# SOURCE_POWER.net
KiCad netlist of a schematic drawn in Altium Designer
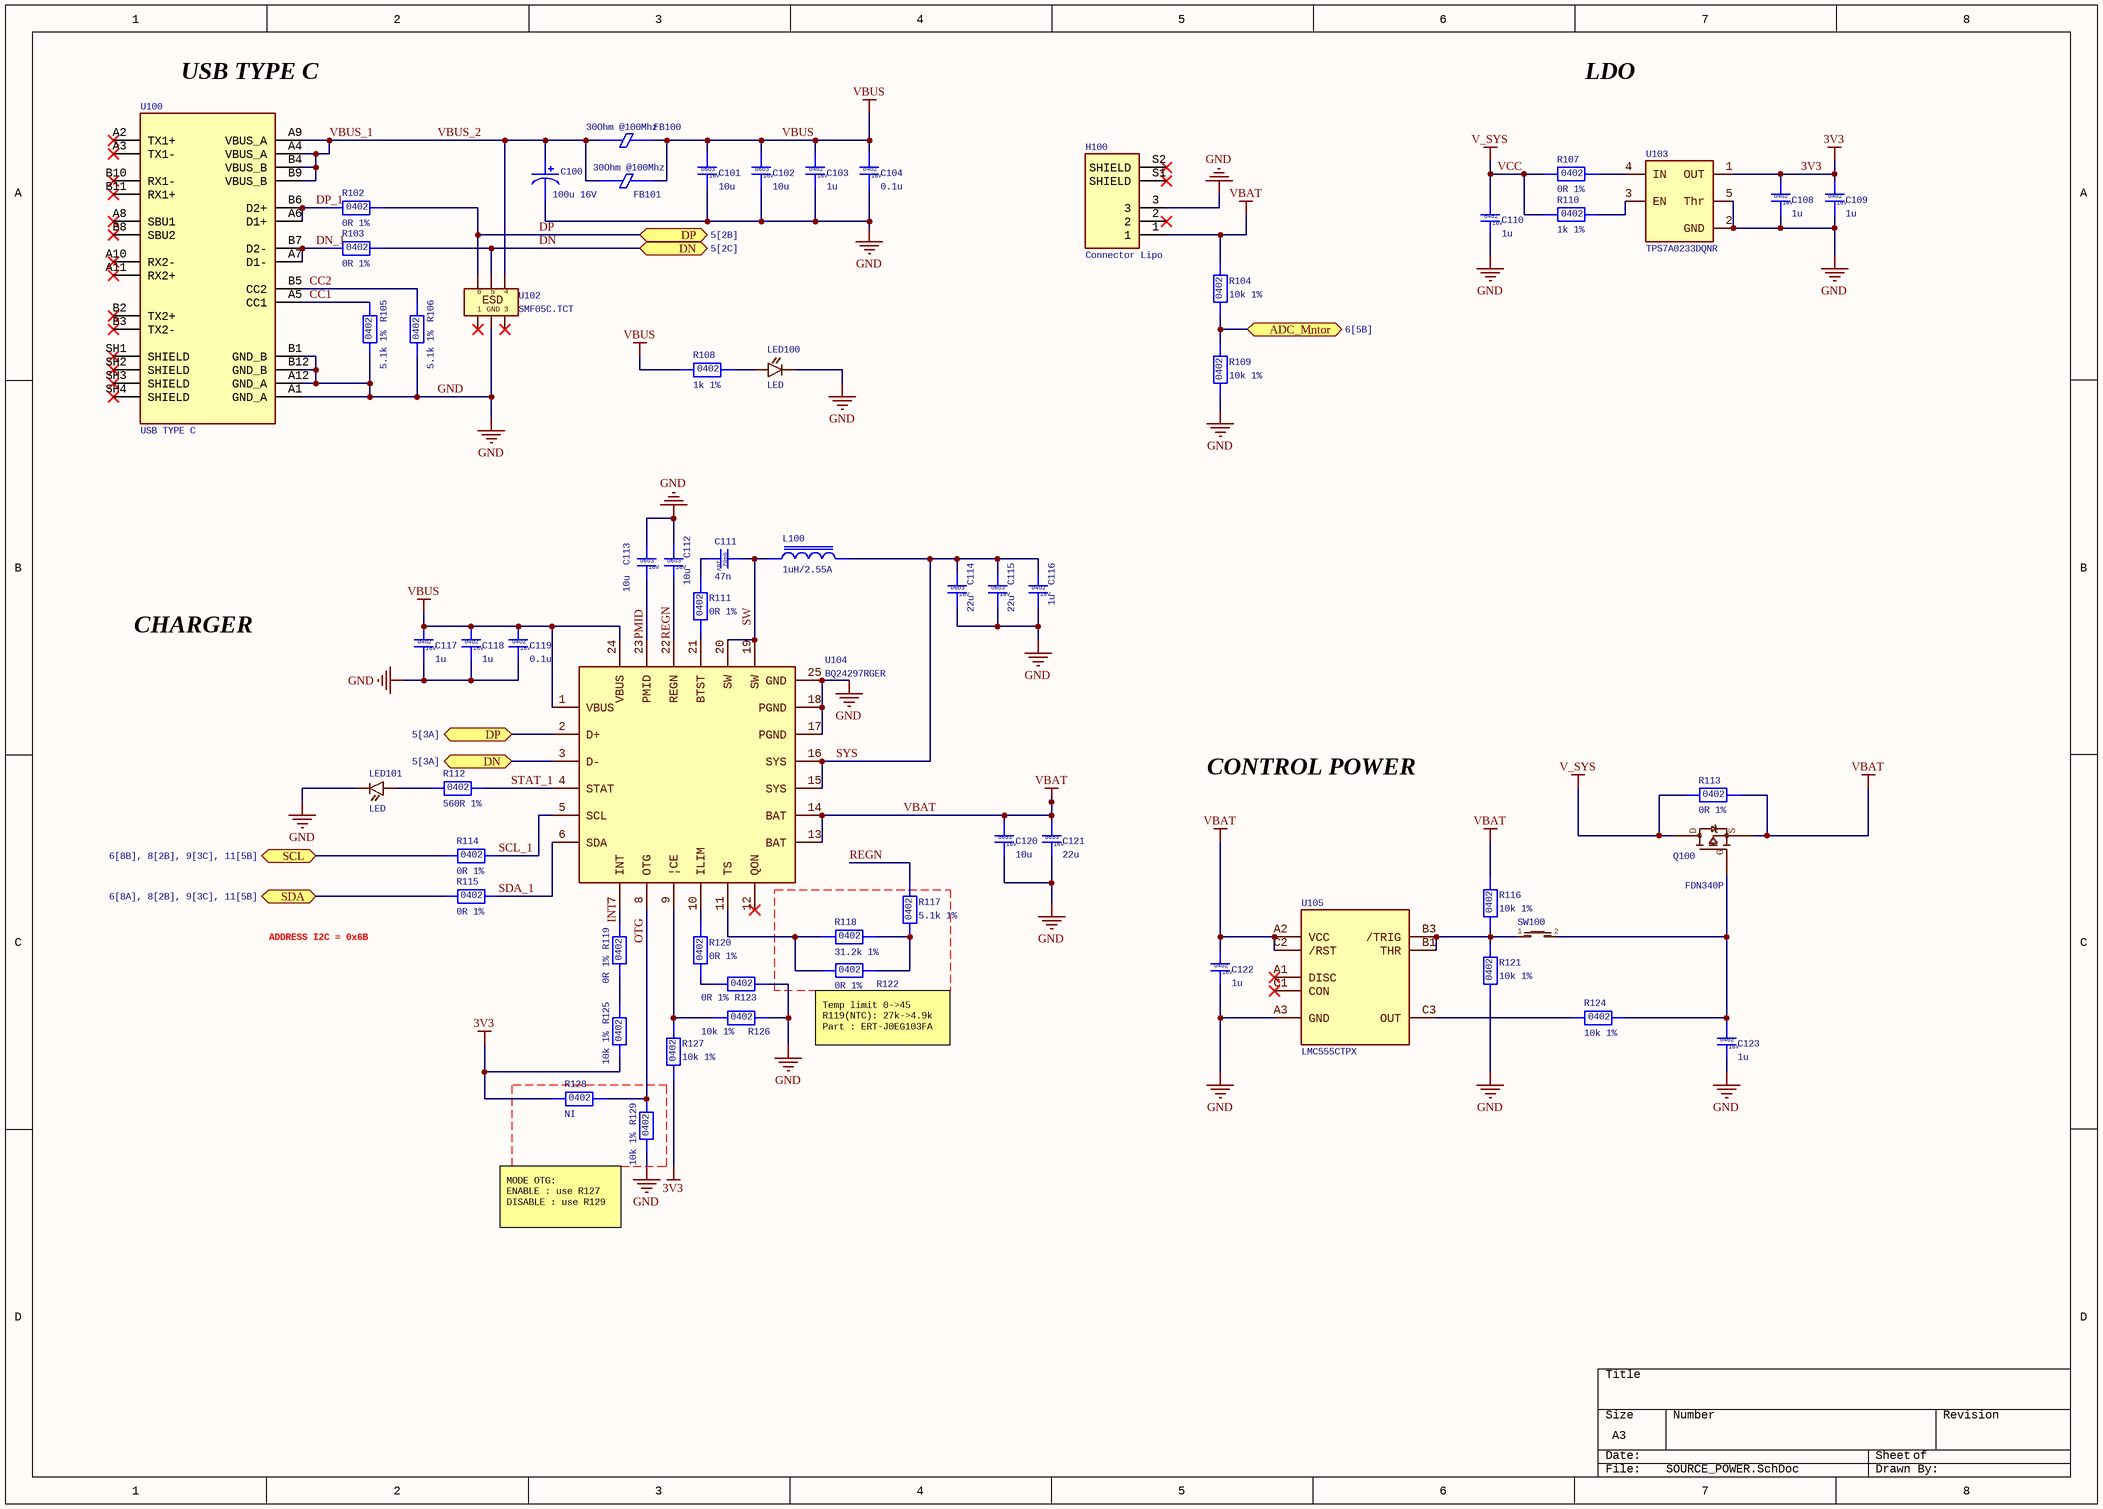
[diagram p0: SOURCE_POWER.SchDoc]

(export (version "E")
  (design (tool "Eeschema 10.0.6"))
  (components
    (comp (ref "C100")
      (value "100u 16V")
      (footprint "T491C107K016AT")
      (fields
        (field (name "MANUFACTURER") "KEMET")
        (field (name "MANUFACTURER PART NUMBER") "T491C107K016AT")
      )
      (libsource (lib "Hw_Lib") (part "T491C107K016AT"))
    )
    (comp (ref "C101")
      (value "10u")
      (footprint "CAP0603")
      (fields
        (field (name "MANUFACTURER") "Murata")
        (field (name "MANUFACTURER PART NUMBER") "GRT188R61C106ME13D")
      )
      (libsource (lib "Hw_Lib") (part "C_0402_10u"))
    )
    (comp (ref "C102")
      (value "10u")
      (footprint "CAP0603")
      (fields
        (field (name "MANUFACTURER") "Murata")
        (field (name "MANUFACTURER PART NUMBER") "GRT188R61C106ME13D")
      )
      (libsource (lib "Hw_Lib") (part "C_0402_10u"))
    )
    (comp (ref "C103")
      (value "1u")
      (footprint "CAP0402")
      (fields
        (field (name "MANUFACTURER") "Taiyo Yuden")
        (field (name "MANUFACTURER PART NUMBER") "EMK105BJ105KV-F")
      )
      (libsource (lib "Hw_Lib") (part "C_0402_1u"))
    )
    (comp (ref "C104")
      (value "0.1u")
      (footprint "CAP0402")
      (fields
        (field (name "MANUFACTURER") "Murata")
        (field (name "MANUFACTURER PART NUMBER") "GRM155R71C104KA88J")
      )
      (libsource (lib "Hw_Lib") (part "C_0402_0.1u"))
    )
    (comp (ref "C108")
      (value "1u")
      (footprint "CAP0402")
      (fields
        (field (name "MANUFACTURER") "Taiyo Yuden")
        (field (name "MANUFACTURER PART NUMBER") "EMK105BJ105KV-F")
      )
      (libsource (lib "Hw_Lib") (part "C_0402_1u"))
    )
    (comp (ref "C109")
      (value "1u")
      (footprint "CAP0402")
      (fields
        (field (name "MANUFACTURER") "Taiyo Yuden")
        (field (name "MANUFACTURER PART NUMBER") "EMK105BJ105KV-F")
      )
      (libsource (lib "Hw_Lib") (part "C_0402_1u"))
    )
    (comp (ref "C110")
      (value "1u")
      (footprint "CAP0402")
      (fields
        (field (name "MANUFACTURER") "Taiyo Yuden")
        (field (name "MANUFACTURER PART NUMBER") "EMK105BJ105KV-F")
      )
      (libsource (lib "Hw_Lib") (part "C_0402_1u"))
    )
    (comp (ref "C111")
      (value "47n")
      (footprint "CAP0402")
      (fields
        (field (name "MANUFACTURER") "Murata")
        (field (name "MANUFACTURER PART NUMBER") "GCM155R71C473KA37D")
      )
      (libsource (lib "Hw_Lib") (part "C_0402_47n"))
    )
    (comp (ref "C112")
      (value "10u")
      (footprint "CAP0603")
      (fields
        (field (name "MANUFACTURER") "Murata")
        (field (name "MANUFACTURER PART NUMBER") "GRT188R61C106ME13D")
      )
      (libsource (lib "Hw_Lib") (part "C_0402_10u"))
    )
    (comp (ref "C113")
      (value "10u")
      (footprint "CAP0603")
      (fields
        (field (name "MANUFACTURER") "Murata")
        (field (name "MANUFACTURER PART NUMBER") "GRT188R61C106ME13D")
      )
      (libsource (lib "Hw_Lib") (part "C_0402_10u"))
    )
    (comp (ref "C114")
      (value "22u")
      (footprint "CAP0603")
      (fields
        (field (name "MANUFACTURER") "Samsung")
        (field (name "MANUFACTURER PART NUMBER") "CL10A226MO7JZNC")
      )
      (libsource (lib "Hw_Lib") (part "C_0402_22u"))
    )
    (comp (ref "C115")
      (value "22u")
      (footprint "CAP0603")
      (fields
        (field (name "MANUFACTURER") "Samsung")
        (field (name "MANUFACTURER PART NUMBER") "CL10A226MO7JZNC")
      )
      (libsource (lib "Hw_Lib") (part "C_0402_22u"))
    )
    (comp (ref "C116")
      (value "1u")
      (footprint "CAP0402")
      (fields
        (field (name "MANUFACTURER") "Taiyo Yuden")
        (field (name "MANUFACTURER PART NUMBER") "EMK105BJ105KV-F")
      )
      (libsource (lib "Hw_Lib") (part "C_0402_1u"))
    )
    (comp (ref "C117")
      (value "1u")
      (footprint "CAP0402")
      (fields
        (field (name "MANUFACTURER") "Taiyo Yuden")
        (field (name "MANUFACTURER PART NUMBER") "EMK105BJ105KV-F")
      )
      (libsource (lib "Hw_Lib") (part "C_0402_1u"))
    )
    (comp (ref "C118")
      (value "1u")
      (footprint "CAP0402")
      (fields
        (field (name "MANUFACTURER") "Taiyo Yuden")
        (field (name "MANUFACTURER PART NUMBER") "EMK105BJ105KV-F")
      )
      (libsource (lib "Hw_Lib") (part "C_0402_1u"))
    )
    (comp (ref "C119")
      (value "0.1u")
      (footprint "CAP0402")
      (fields
        (field (name "MANUFACTURER") "Murata")
        (field (name "MANUFACTURER PART NUMBER") "GRM155R71C104KA88J")
      )
      (libsource (lib "Hw_Lib") (part "C_0402_0.1u"))
    )
    (comp (ref "C120")
      (value "10u")
      (footprint "CAP0603")
      (fields
        (field (name "MANUFACTURER") "Murata")
        (field (name "MANUFACTURER PART NUMBER") "GRT188R61C106ME13D")
      )
      (libsource (lib "Hw_Lib") (part "C_0402_10u"))
    )
    (comp (ref "C121")
      (value "22u")
      (footprint "CAP0603")
      (fields
        (field (name "MANUFACTURER") "Samsung")
        (field (name "MANUFACTURER PART NUMBER") "CL10A226MO7JZNC")
      )
      (libsource (lib "Hw_Lib") (part "C_0402_22u"))
    )
    (comp (ref "C122")
      (value "1u")
      (footprint "CAP0402")
      (fields
        (field (name "MANUFACTURER") "Taiyo Yuden")
        (field (name "MANUFACTURER PART NUMBER") "EMK105BJ105KV-F")
      )
      (libsource (lib "Hw_Lib") (part "C_0402_1u"))
    )
    (comp (ref "C123")
      (value "1u")
      (footprint "CAP0402")
      (fields
        (field (name "MANUFACTURER") "Taiyo Yuden")
        (field (name "MANUFACTURER PART NUMBER") "EMK105BJ105KV-F")
      )
      (libsource (lib "Hw_Lib") (part "C_0402_1u"))
    )
    (comp (ref "FB100")
      (value "30Ohm @100Mhz")
      (footprint "FB0402")
      (description "Ferrite Chip, 1 Function(s), 1.4A, 2 Pin(s)")
      (fields
        (field (name "MANUFACTURER") "Murata")
        (field (name "MANUFACTURER PART NUMBER") "BLM15PD300SN1D")
      )
      (libsource (lib "Hw_Lib") (part "BLM15PD300SN1D"))
    )
    (comp (ref "FB101")
      (value "30Ohm @100Mhz")
      (footprint "FB0402")
      (description "Ferrite Chip, 1 Function(s), 1.4A, 2 Pin(s)")
      (fields
        (field (name "MANUFACTURER") "Murata")
        (field (name "MANUFACTURER PART NUMBER") "BLM15PD300SN1D")
      )
      (libsource (lib "Hw_Lib") (part "BLM15PD300SN1D"))
    )
    (comp (ref "H100")
      (value "Connector Lipo")
      (footprint "CON")
      (description "CONN HEADER SH 3POS SIDE 1MM TIN")
      (fields
        (field (name "MANUFACTURER") "JST")
        (field (name "MANUFACTURER PART NUMBER") "SM03B-SRSS-TB(LF)(SN)")
      )
      (libsource (lib "Hw_Lib") (part "Connector Lipo"))
    )
    (comp (ref "L100")
      (value "1uH/2.55A")
      (footprint "VLS2012ET-1R0N-CA")
      (description "FIXED IND 1UH 1.65A 86 MOHM SMD")
      (libsource (lib "Hw_Lib") (part "VLS2012ET-1R0N-CA"))
    )
    (comp (ref "LED100")
      (value "LED")
      (footprint "LED0402")
      (description "Single Color LED, Hyper Red, Water Clear, 0.8mm")
      (fields
        (field (name "MANUFACTURER") "Kingbright")
        (field (name "MANUFACTURER PART NUMBER") "APHHS1005SURCK")
      )
      (libsource (lib "Hw_Lib") (part "LED0402"))
    )
    (comp (ref "LED101")
      (value "LED")
      (footprint "LED0402")
      (description "Single Color LED, Hyper Red, Water Clear, 0.8mm")
      (fields
        (field (name "MANUFACTURER") "Kingbright")
        (field (name "MANUFACTURER PART NUMBER") "APHHS1005SURCK")
      )
      (libsource (lib "Hw_Lib") (part "LED0402"))
    )
    (comp (ref "Q100")
      (value "FDN340P")
      (footprint "FDN340P")
      (fields (field (name "MANUFACTURER") "ON Semiconductor / Fairchild"))
      (libsource (lib "Hw_Lib") (part "FDN340P"))
    )
    (comp (ref "R102")
      (value "0R 1%")
      (footprint "RES0402")
      (description "Metal Glaze/thick Film, 0.0625W, 0ohm, Surface Mount, 0402")
      (fields
        (field (name "MANUFACTURER") "Yageo")
        (field (name "MANUFACTURER PART NUMBER") "RC0402JR-070RL")
      )
      (libsource (lib "Hw_Lib") (part "R_0402_0R"))
    )
    (comp (ref "R103")
      (value "0R 1%")
      (footprint "RES0402")
      (description "Metal Glaze/thick Film, 0.0625W, 0ohm, Surface Mount, 0402")
      (fields
        (field (name "MANUFACTURER") "Yageo")
        (field (name "MANUFACTURER PART NUMBER") "RC0402JR-070RL")
      )
      (libsource (lib "Hw_Lib") (part "R_0402_0R"))
    )
    (comp (ref "R104")
      (value "10k 1%")
      (footprint "R0402")
      (fields
        (field (name "MANUFACTURER") "Samsung")
        (field (name "MANUFACTURER PART NUMBER") "RC1005F103CS")
        (field (name "TOLERANCE") "1%")
      )
      (libsource (lib "Hw_Lib") (part "R_0402_10k"))
    )
    (comp (ref "R105")
      (value "5.1k 1%")
      (footprint "RES0402")
      (fields
        (field (name "MANUFACTURER") "Yageo")
        (field (name "MANUFACTURER PART NUMBER") "RC0402FR-075K1L")
        (field (name "TOLERANCE") "1%")
      )
      (libsource (lib "Hw_Lib") (part "R_0402_5.1k"))
    )
    (comp (ref "R106")
      (value "5.1k 1%")
      (footprint "RES0402")
      (fields
        (field (name "MANUFACTURER") "Yageo")
        (field (name "MANUFACTURER PART NUMBER") "RC0402FR-075K1L")
        (field (name "TOLERANCE") "1%")
      )
      (libsource (lib "Hw_Lib") (part "R_0402_5.1k"))
    )
    (comp (ref "R107")
      (value "0R 1%")
      (footprint "RES0402")
      (description "Metal Glaze/thick Film, 0.0625W, 0ohm, Surface Mount, 0402")
      (fields
        (field (name "MANUFACTURER") "Yageo")
        (field (name "MANUFACTURER PART NUMBER") "RC0402JR-070RL")
      )
      (libsource (lib "Hw_Lib") (part "R_0402_0R"))
    )
    (comp (ref "R108")
      (value "1k 1%")
      (footprint "RES0402")
      (fields
        (field (name "MANUFACTURER") "KOA Speer")
        (field (name "MANUFACTURER PART NUMBER") "RK73H1ETTP1001F")
        (field (name "TOLERANCE") "1%")
      )
      (libsource (lib "Hw_Lib") (part "R_0402_1k"))
    )
    (comp (ref "R109")
      (value "10k 1%")
      (footprint "R0402")
      (fields
        (field (name "MANUFACTURER") "Samsung")
        (field (name "MANUFACTURER PART NUMBER") "RC1005F103CS")
        (field (name "TOLERANCE") "1%")
      )
      (libsource (lib "Hw_Lib") (part "R_0402_10k"))
    )
    (comp (ref "R110")
      (value "1k 1%")
      (footprint "RES0402")
      (fields
        (field (name "MANUFACTURER") "KOA Speer")
        (field (name "MANUFACTURER PART NUMBER") "RK73H1ETTP1001F")
        (field (name "TOLERANCE") "1%")
      )
      (libsource (lib "Hw_Lib") (part "R_0402_1k"))
    )
    (comp (ref "R111")
      (value "0R 1%")
      (footprint "RES0402")
      (description "Metal Glaze/thick Film, 0.0625W, 0ohm, Surface Mount, 0402")
      (fields
        (field (name "MANUFACTURER") "Yageo")
        (field (name "MANUFACTURER PART NUMBER") "RC0402JR-070RL")
      )
      (libsource (lib "Hw_Lib") (part "R_0402_0R"))
    )
    (comp (ref "R112")
      (value "560R 1%")
      (footprint "R0402")
      (fields
        (field (name "MANUFACTURER") "KOA Speer")
        (field (name "MANUFACTURER PART NUMBER") "RK73H1ETTP5600F")
        (field (name "TOLERANCE") "1%")
      )
      (libsource (lib "Hw_Lib") (part "R_0402_560R"))
    )
    (comp (ref "R113")
      (value "0R 1%")
      (footprint "RES0402")
      (description "Metal Glaze/thick Film, 0.0625W, 0ohm, Surface Mount, 0402")
      (fields
        (field (name "MANUFACTURER") "Yageo")
        (field (name "MANUFACTURER PART NUMBER") "RC0402JR-070RL")
      )
      (libsource (lib "Hw_Lib") (part "R_0402_0R"))
    )
    (comp (ref "R114")
      (value "0R 1%")
      (footprint "RES0402")
      (description "Metal Glaze/thick Film, 0.0625W, 0ohm, Surface Mount, 0402")
      (fields
        (field (name "MANUFACTURER") "Yageo")
        (field (name "MANUFACTURER PART NUMBER") "RC0402JR-070RL")
      )
      (libsource (lib "Hw_Lib") (part "R_0402_0R"))
    )
    (comp (ref "R115")
      (value "0R 1%")
      (footprint "RES0402")
      (description "Metal Glaze/thick Film, 0.0625W, 0ohm, Surface Mount, 0402")
      (fields
        (field (name "MANUFACTURER") "Yageo")
        (field (name "MANUFACTURER PART NUMBER") "RC0402JR-070RL")
      )
      (libsource (lib "Hw_Lib") (part "R_0402_0R"))
    )
    (comp (ref "R116")
      (value "10k 1%")
      (footprint "R0402")
      (fields
        (field (name "MANUFACTURER") "Samsung")
        (field (name "MANUFACTURER PART NUMBER") "RC1005F103CS")
        (field (name "TOLERANCE") "1%")
      )
      (libsource (lib "Hw_Lib") (part "R_0402_10k"))
    )
    (comp (ref "R117")
      (value "5.1k 1%")
      (footprint "RES0402")
      (fields
        (field (name "MANUFACTURER") "Yageo")
        (field (name "MANUFACTURER PART NUMBER") "RC0402FR-075K1L")
        (field (name "TOLERANCE") "1%")
      )
      (libsource (lib "Hw_Lib") (part "R_0402_5.1k"))
    )
    (comp (ref "R118")
      (value "31.2k 1%")
      (footprint "RES0402")
      (description "Fixed Resistor, Thin Film, 0.063W, 31200ohm, 50V, 1% +/-Tol, 25ppm/Cel, Surface Mount, 0402")
      (fields
        (field (name "MANUFACTURER") "KOA Speer")
        (field (name "MANUFACTURER PART NUMBER") "RN73H1ETTP3122F25")
      )
      (libsource (lib "Hw_Lib") (part "R_0402_31.2k"))
    )
    (comp (ref "R119")
      (value "0R 1%")
      (footprint "RES0402")
      (description "Metal Glaze/thick Film, 0.0625W, 0ohm, Surface Mount, 0402")
      (fields
        (field (name "MANUFACTURER") "Yageo")
        (field (name "MANUFACTURER PART NUMBER") "RC0402JR-070RL")
      )
      (libsource (lib "Hw_Lib") (part "R_0402_0R"))
    )
    (comp (ref "R120")
      (value "0R 1%")
      (footprint "RES0402")
      (description "Metal Glaze/thick Film, 0.0625W, 0ohm, Surface Mount, 0402")
      (fields
        (field (name "MANUFACTURER") "Yageo")
        (field (name "MANUFACTURER PART NUMBER") "RC0402JR-070RL")
      )
      (libsource (lib "Hw_Lib") (part "R_0402_0R"))
    )
    (comp (ref "R121")
      (value "10k 1%")
      (footprint "R0402")
      (fields
        (field (name "MANUFACTURER") "Samsung")
        (field (name "MANUFACTURER PART NUMBER") "RC1005F103CS")
        (field (name "TOLERANCE") "1%")
      )
      (libsource (lib "Hw_Lib") (part "R_0402_10k"))
    )
    (comp (ref "R122")
      (value "0R 1%")
      (footprint "RES0402")
      (description "Metal Glaze/thick Film, 0.0625W, 0ohm, Surface Mount, 0402")
      (fields
        (field (name "MANUFACTURER") "Yageo")
        (field (name "MANUFACTURER PART NUMBER") "RC0402JR-070RL")
      )
      (libsource (lib "Hw_Lib") (part "R_0402_0R"))
    )
    (comp (ref "R123")
      (value "0R 1%")
      (footprint "RES0402")
      (description "Metal Glaze/thick Film, 0.0625W, 0ohm, Surface Mount, 0402")
      (fields
        (field (name "MANUFACTURER") "Yageo")
        (field (name "MANUFACTURER PART NUMBER") "RC0402JR-070RL")
      )
      (libsource (lib "Hw_Lib") (part "R_0402_0R"))
    )
    (comp (ref "R124")
      (value "10k 1%")
      (footprint "R0402")
      (fields
        (field (name "MANUFACTURER") "Samsung")
        (field (name "MANUFACTURER PART NUMBER") "RC1005F103CS")
        (field (name "TOLERANCE") "1%")
      )
      (libsource (lib "Hw_Lib") (part "R_0402_10k"))
    )
    (comp (ref "R125")
      (value "10k 1%")
      (footprint "R0402")
      (fields
        (field (name "MANUFACTURER") "Samsung")
        (field (name "MANUFACTURER PART NUMBER") "RC1005F103CS")
        (field (name "TOLERANCE") "1%")
      )
      (libsource (lib "Hw_Lib") (part "R_0402_10k"))
    )
    (comp (ref "R126")
      (value "10k 1%")
      (footprint "R0402")
      (fields
        (field (name "MANUFACTURER") "Samsung")
        (field (name "MANUFACTURER PART NUMBER") "RC1005F103CS")
        (field (name "TOLERANCE") "1%")
      )
      (libsource (lib "Hw_Lib") (part "R_0402_10k"))
    )
    (comp (ref "R127")
      (value "10k 1%")
      (footprint "R0402")
      (fields
        (field (name "MANUFACTURER") "Samsung")
        (field (name "MANUFACTURER PART NUMBER") "RC1005F103CS")
        (field (name "TOLERANCE") "1%")
      )
      (libsource (lib "Hw_Lib") (part "R_0402_10k"))
    )
    (comp (ref "R128")
      (value "NI")
      (footprint "RES0402")
      (description "Metal Glaze/thick Film, 0.0625W, 0ohm, Surface Mount, 0402")
      (fields
        (field (name "MANUFACTURER") "Yageo")
        (field (name "MANUFACTURER PART NUMBER") "RC0402JR-070RL")
      )
      (libsource (lib "Hw_Lib") (part "R_0402_0R"))
    )
    (comp (ref "R129")
      (value "10k 1%")
      (footprint "R0402")
      (fields
        (field (name "MANUFACTURER") "Samsung")
        (field (name "MANUFACTURER PART NUMBER") "RC1005F103CS")
        (field (name "TOLERANCE") "1%")
      )
      (libsource (lib "Hw_Lib") (part "R_0402_10k"))
    )
    (comp (ref "SW100")
      (value "SW")
      (footprint "434331013822")
      (description "SWITCH TACTILE SPST-NO 0.05A 12V")
      (libsource (lib "Hw_Lib") (part "434331013822"))
    )
    (comp (ref "U100")
      (value "USB TYPE C")
      (footprint "12401826E412A")
      (description "USB3.2 GEN2, Type C, Top mount, CH 1.58mm, Dual Row SMT / Tap/Rl RoHS Compliant: Yes")
      (fields
        (field (name "MANUFACTURER") "Amphenol Communications Solutions")
        (field (name "MANUFACTURER PART NUMBER") "12401826E412A")
      )
      (libsource (lib "Hw_Lib") (part "USBC_12401826E412A"))
    )
    (comp (ref "U102")
      (value "SMF05C.TCT")
      (footprint "SMF05C.TCT")
      (description "Trans Voltage Suppressor Diode, 100W, 5V V(RWM), Unidirectional, 5 Element, Silicon, MO-203AB")
      (fields (field (name "MANUFACTURER") "Semtech"))
      (libsource (lib "Hw_Lib") (part "SMF05C.TCT"))
    )
    (comp (ref "U103")
      (value "TPS7A0233DQNR")
      (footprint "TPS7A0218PDQNR")
      (description "IC REG LINEAR 3V3 200MA 4X2SON")
      (libsource (lib "Hw_Lib") (part "TPS7A0233DQNR"))
    )
    (comp (ref "U104")
      (value "BQ24297RGER")
      (footprint "BQ24297RGER")
      (description "Power Supply Management Circuit, Adjustable, 1 Channel, +6.4V, PQCC24")
      (fields (field (name "MANUFACTURER") "Texas Instruments"))
      (libsource (lib "Hw_Lib") (part "BQ24297RGER"))
    )
    (comp (ref "U105")
      (value "LMC555CTPX")
      (footprint "LMC555CTPX/NOPB")
      (description "1 Func, 3MHz, CMOS, PBGA8")
      (fields
        (field (name "MANUFACTURER") "TI National Semiconductor")
        (field (name "MANUFACTURER PART NUMBER") "LMC555CTPX/NOPB")
      )
      (libsource (lib "Hw_Lib") (part "LMC555CTPX/NOPB"))
    )
  )
  (nets
    (net (code "1") (name "/ADC_Mntor") (class "Default")
      (node (ref "R104") (pin "1") (pinfunction "1_1") (pintype "passive"))
      (node (ref "R109") (pin "2") (pinfunction "2_2") (pintype "passive"))
    )
    (net (code "2") (name "/CC1") (class "Default")
      (node (ref "R105") (pin "2") (pinfunction "2_2") (pintype "passive"))
      (node (ref "U100") (pin "A5") (pinfunction "CC1_A5") (pintype "open_collector"))
    )
    (net (code "3") (name "/CC2") (class "Default")
      (node (ref "R106") (pin "2") (pinfunction "2_2") (pintype "passive"))
      (node (ref "U100") (pin "B5") (pinfunction "CC2_B5") (pintype "open_collector"))
    )
    (net (code "4") (name "/DN") (class "Default")
      (node (ref "R103") (pin "2") (pinfunction "2_2") (pintype "passive"))
      (node (ref "U102") (pin "5") (pinfunction "5_5") (pintype "passive"))
      (node (ref "U104") (pin "3") (pinfunction "D-_3") (pintype "passive"))
    )
    (net (code "5") (name "/DN_1") (class "Default")
      (node (ref "R103") (pin "1") (pinfunction "1_1") (pintype "passive"))
      (node (ref "U100") (pin "A7") (pinfunction "D1-_A7") (pintype "open_collector"))
      (node (ref "U100") (pin "B7") (pinfunction "D2-_B7") (pintype "open_collector"))
    )
    (net (code "6") (name "/DP") (class "Default")
      (node (ref "R102") (pin "2") (pinfunction "2_2") (pintype "passive"))
      (node (ref "U102") (pin "6") (pinfunction "6_6") (pintype "passive"))
      (node (ref "U104") (pin "2") (pinfunction "D+_2") (pintype "passive"))
    )
    (net (code "7") (name "/DP_1") (class "Default")
      (node (ref "R102") (pin "1") (pinfunction "1_1") (pintype "passive"))
      (node (ref "U100") (pin "A6") (pinfunction "D1+_A6") (pintype "open_collector"))
      (node (ref "U100") (pin "B6") (pinfunction "D2+_B6") (pintype "open_collector"))
    )
    (net (code "8") (name "/INT") (class "Default")
      (node (ref "R119") (pin "2") (pinfunction "2_2") (pintype "passive"))
      (node (ref "U104") (pin "7") (pinfunction "INT_7") (pintype "passive"))
    )
    (net (code "9") (name "/OTG") (class "Default")
      (node (ref "R128") (pin "2") (pinfunction "2_2") (pintype "passive"))
      (node (ref "R129") (pin "2") (pinfunction "2_2") (pintype "passive"))
      (node (ref "U104") (pin "8") (pinfunction "OTG_8") (pintype "passive"))
    )
    (net (code "10") (name "/PMID") (class "Default")
      (node (ref "C113") (pin "2") (pinfunction "2_2") (pintype "passive"))
      (node (ref "U104") (pin "23") (pinfunction "PMID_23") (pintype "passive"))
    )
    (net (code "11") (name "/REGN") (class "Default")
      (node (ref "C112") (pin "2") (pinfunction "2_2") (pintype "passive"))
      (node (ref "R117") (pin "2") (pinfunction "2_2") (pintype "passive"))
      (node (ref "U104") (pin "22") (pinfunction "REGN_22") (pintype "passive"))
    )
    (net (code "12") (name "/SCL") (class "Default")
      (node (ref "R114") (pin "1") (pinfunction "1_1") (pintype "passive"))
    )
    (net (code "13") (name "/SCL_1") (class "Default")
      (node (ref "R114") (pin "2") (pinfunction "2_2") (pintype "passive"))
      (node (ref "U104") (pin "5") (pinfunction "SCL_5") (pintype "passive"))
    )
    (net (code "14") (name "/SDA") (class "Default")
      (node (ref "R115") (pin "1") (pinfunction "1_1") (pintype "passive"))
    )
    (net (code "15") (name "/SDA_1") (class "Default")
      (node (ref "R115") (pin "2") (pinfunction "2_2") (pintype "passive"))
      (node (ref "U104") (pin "6") (pinfunction "SDA_6") (pintype "passive"))
    )
    (net (code "16") (name "/STAT_1") (class "Default")
      (node (ref "R112") (pin "2") (pinfunction "2_2") (pintype "passive"))
      (node (ref "U104") (pin "4") (pinfunction "STAT_4") (pintype "passive"))
    )
    (net (code "17") (name "/SW") (class "Default")
      (node (ref "C111") (pin "1") (pinfunction "1_1") (pintype "passive"))
      (node (ref "L100") (pin "1") (pinfunction "1_1") (pintype "passive"))
      (node (ref "U104") (pin "19") (pinfunction "SW_19") (pintype "passive"))
      (node (ref "U104") (pin "20") (pinfunction "SW_20") (pintype "passive"))
    )
    (net (code "18") (name "/SYS") (class "Default")
      (node (ref "C114") (pin "1") (pinfunction "1_1") (pintype "passive"))
      (node (ref "C115") (pin "1") (pinfunction "1_1") (pintype "passive"))
      (node (ref "C116") (pin "1") (pinfunction "1_1") (pintype "passive"))
      (node (ref "L100") (pin "2") (pinfunction "2_2") (pintype "passive"))
      (node (ref "U104") (pin "15") (pinfunction "SYS_15") (pintype "passive"))
      (node (ref "U104") (pin "16") (pinfunction "SYS_16") (pintype "passive"))
    )
    (net (code "19") (name "/VBUS_1") (class "Default")
      (node (ref "C100") (pin "A") (pinfunction "3_A") (pintype "passive"))
      (node (ref "FB100") (pin "1") (pinfunction "1_1") (pintype "passive"))
      (node (ref "FB101") (pin "1") (pinfunction "1_1") (pintype "passive"))
      (node (ref "U100") (pin "A4") (pinfunction "VBUS_A_A4") (pintype "open_collector"))
      (node (ref "U100") (pin "A9") (pinfunction "VBUS_A_A9") (pintype "open_collector"))
      (node (ref "U100") (pin "B4") (pinfunction "VBUS_B_B4") (pintype "open_collector"))
      (node (ref "U100") (pin "B9") (pinfunction "VBUS_B_B9") (pintype "open_collector"))
      (node (ref "U102") (pin "4") (pinfunction "4_4") (pintype "passive"))
    )
    (net (code "20") (name "3V3") (class "Default")
      (node (ref "C108") (pin "1") (pinfunction "1_1") (pintype "passive"))
      (node (ref "C109") (pin "1") (pinfunction "1_1") (pintype "passive"))
      (node (ref "R125") (pin "1") (pinfunction "1_1") (pintype "passive"))
      (node (ref "R127") (pin "1") (pinfunction "1_1") (pintype "passive"))
      (node (ref "R128") (pin "1") (pinfunction "1_1") (pintype "passive"))
      (node (ref "U103") (pin "1") (pinfunction "OUT_1") (pintype "passive"))
    )
    (net (code "21") (name "GND") (class "Default")
      (node (ref "C100") (pin "C") (pinfunction "4_C") (pintype "passive"))
      (node (ref "C101") (pin "2") (pinfunction "2_2") (pintype "passive"))
      (node (ref "C102") (pin "2") (pinfunction "2_2") (pintype "passive"))
      (node (ref "C103") (pin "2") (pinfunction "2_2") (pintype "passive"))
      (node (ref "C104") (pin "2") (pinfunction "2_2") (pintype "passive"))
      (node (ref "C108") (pin "2") (pinfunction "2_2") (pintype "passive"))
      (node (ref "C109") (pin "2") (pinfunction "2_2") (pintype "passive"))
      (node (ref "C110") (pin "2") (pinfunction "2_2") (pintype "passive"))
      (node (ref "C112") (pin "1") (pinfunction "1_1") (pintype "passive"))
      (node (ref "C113") (pin "1") (pinfunction "1_1") (pintype "passive"))
      (node (ref "C114") (pin "2") (pinfunction "2_2") (pintype "passive"))
      (node (ref "C115") (pin "2") (pinfunction "2_2") (pintype "passive"))
      (node (ref "C116") (pin "2") (pinfunction "2_2") (pintype "passive"))
      (node (ref "C117") (pin "2") (pinfunction "2_2") (pintype "passive"))
      (node (ref "C118") (pin "2") (pinfunction "2_2") (pintype "passive"))
      (node (ref "C119") (pin "2") (pinfunction "2_2") (pintype "passive"))
      (node (ref "C120") (pin "2") (pinfunction "2_2") (pintype "passive"))
      (node (ref "C121") (pin "2") (pinfunction "2_2") (pintype "passive"))
      (node (ref "C122") (pin "2") (pinfunction "2_2") (pintype "passive"))
      (node (ref "C123") (pin "2") (pinfunction "2_2") (pintype "passive"))
      (node (ref "H100") (pin "3") (pinfunction "3_3") (pintype "passive"))
      (node (ref "LED100") (pin "1") (pinfunction "C_1") (pintype "passive"))
      (node (ref "LED101") (pin "1") (pinfunction "C_1") (pintype "passive"))
      (node (ref "R105") (pin "1") (pinfunction "1_1") (pintype "passive"))
      (node (ref "R106") (pin "1") (pinfunction "1_1") (pintype "passive"))
      (node (ref "R109") (pin "1") (pinfunction "1_1") (pintype "passive"))
      (node (ref "R121") (pin "1") (pinfunction "1_1") (pintype "passive"))
      (node (ref "R123") (pin "2") (pinfunction "2_2") (pintype "passive"))
      (node (ref "R126") (pin "2") (pinfunction "2_2") (pintype "passive"))
      (node (ref "R129") (pin "1") (pinfunction "1_1") (pintype "passive"))
      (node (ref "U100") (pin "A1") (pinfunction "GND_A_A1") (pintype "open_collector"))
      (node (ref "U100") (pin "A12") (pinfunction "GND_A_A12") (pintype "open_collector"))
      (node (ref "U100") (pin "B1") (pinfunction "GND_B_B1") (pintype "open_collector"))
      (node (ref "U100") (pin "B12") (pinfunction "GND_B_B12") (pintype "open_collector"))
      (node (ref "U102") (pin "2") (pinfunction "2_2") (pintype "passive"))
      (node (ref "U103") (pin "2") (pinfunction "GND_2") (pintype "passive"))
      (node (ref "U103") (pin "5") (pinfunction "Thr_5") (pintype "passive"))
      (node (ref "U104") (pin "17") (pinfunction "PGND_17") (pintype "passive"))
      (node (ref "U104") (pin "18") (pinfunction "PGND_18") (pintype "passive"))
      (node (ref "U104") (pin "25") (pinfunction "GND_25") (pintype "passive"))
      (node (ref "U105") (pin "A3") (pinfunction "GND_A3") (pintype "passive"))
    )
    (net (code "22") (name "Net-(C111-Pad2)") (class "Default")
      (node (ref "C111") (pin "2") (pinfunction "2_2") (pintype "passive"))
      (node (ref "R111") (pin "2") (pinfunction "2_2") (pintype "passive"))
    )
    (net (code "23") (name "Net-(LED100-A)") (class "Default")
      (node (ref "LED100") (pin "2") (pinfunction "A_2") (pintype "passive"))
      (node (ref "R108") (pin "2") (pinfunction "2_2") (pintype "passive"))
    )
    (net (code "24") (name "Net-(LED101-A)") (class "Default")
      (node (ref "LED101") (pin "2") (pinfunction "A_2") (pintype "passive"))
      (node (ref "R112") (pin "1") (pinfunction "1_1") (pintype "passive"))
    )
    (net (code "25") (name "Net-(Q100-G)") (class "Default")
      (node (ref "C123") (pin "1") (pinfunction "1_1") (pintype "passive"))
      (node (ref "Q100") (pin "1") (pinfunction "G_1") (pintype "passive"))
      (node (ref "R124") (pin "2") (pinfunction "2_2") (pintype "passive"))
      (node (ref "SW100") (pin "2") (pinfunction "2_2") (pintype "passive"))
    )
    (net (code "26") (name "Net-(R117-Pad1)") (class "Default")
      (node (ref "R117") (pin "1") (pinfunction "1_1") (pintype "passive"))
      (node (ref "R118") (pin "2") (pinfunction "2_2") (pintype "passive"))
      (node (ref "R122") (pin "2") (pinfunction "2_2") (pintype "passive"))
    )
    (net (code "27") (name "Net-(R119-Pad1)") (class "Default")
      (node (ref "R119") (pin "1") (pinfunction "1_1") (pintype "passive"))
      (node (ref "R125") (pin "2") (pinfunction "2_2") (pintype "passive"))
    )
    (net (code "28") (name "Net-(R120-Pad1)") (class "Default")
      (node (ref "R120") (pin "1") (pinfunction "1_1") (pintype "passive"))
      (node (ref "R123") (pin "1") (pinfunction "1_1") (pintype "passive"))
    )
    (net (code "29") (name "Net-(U103-EN)") (class "Default")
      (node (ref "R110") (pin "2") (pinfunction "2_2") (pintype "passive"))
      (node (ref "U103") (pin "3") (pinfunction "EN_3") (pintype "passive"))
    )
    (net (code "30") (name "Net-(U103-IN)") (class "Default")
      (node (ref "R107") (pin "2") (pinfunction "2_2") (pintype "passive"))
      (node (ref "U103") (pin "4") (pinfunction "IN_4") (pintype "passive"))
    )
    (net (code "31") (name "Net-(U104-BTST)") (class "Default")
      (node (ref "R111") (pin "1") (pinfunction "1_1") (pintype "passive"))
      (node (ref "U104") (pin "21") (pinfunction "BTST_21") (pintype "passive"))
    )
    (net (code "32") (name "Net-(U104-ILIM)") (class "Default")
      (node (ref "R120") (pin "2") (pinfunction "2_2") (pintype "passive"))
      (node (ref "U104") (pin "10") (pinfunction "ILIM_10") (pintype "passive"))
    )
    (net (code "33") (name "Net-(U104-TS)") (class "Default")
      (node (ref "R118") (pin "1") (pinfunction "1_1") (pintype "passive"))
      (node (ref "R122") (pin "1") (pinfunction "1_1") (pintype "passive"))
      (node (ref "U104") (pin "11") (pinfunction "TS_11") (pintype "passive"))
    )
    (net (code "34") (name "Net-(U104-¦CE)") (class "Default")
      (node (ref "R126") (pin "1") (pinfunction "1_1") (pintype "passive"))
      (node (ref "R127") (pin "2") (pinfunction "2_2") (pintype "passive"))
      (node (ref "U104") (pin "9") (pinfunction "¦CE_9") (pintype "passive"))
    )
    (net (code "35") (name "Net-(U105-OUT)") (class "Default")
      (node (ref "R124") (pin "1") (pinfunction "1_1") (pintype "passive"))
      (node (ref "U105") (pin "C3") (pinfunction "OUT_C3") (pintype "passive"))
    )
    (net (code "36") (name "Net-(U105-THR)") (class "Default")
      (node (ref "R116") (pin "1") (pinfunction "1_1") (pintype "passive"))
      (node (ref "R121") (pin "2") (pinfunction "2_2") (pintype "passive"))
      (node (ref "SW100") (pin "1") (pinfunction "1_1") (pintype "passive"))
      (node (ref "U105") (pin "B1") (pinfunction "THR_B1") (pintype "passive"))
      (node (ref "U105") (pin "B3") (pinfunction "/TRIG_B3") (pintype "passive"))
    )
    (net (code "37") (name "VBAT") (class "Default")
      (node (ref "C120") (pin "1") (pinfunction "1_1") (pintype "passive"))
      (node (ref "C121") (pin "1") (pinfunction "1_1") (pintype "passive"))
      (node (ref "C122") (pin "1") (pinfunction "1_1") (pintype "passive"))
      (node (ref "H100") (pin "1") (pinfunction "1_1") (pintype "passive"))
      (node (ref "Q100") (pin "2") (pinfunction "S_2") (pintype "passive"))
      (node (ref "R104") (pin "2") (pinfunction "2_2") (pintype "passive"))
      (node (ref "R113") (pin "2") (pinfunction "2_2") (pintype "passive"))
      (node (ref "R116") (pin "2") (pinfunction "2_2") (pintype "passive"))
      (node (ref "U104") (pin "13") (pinfunction "BAT_13") (pintype "passive"))
      (node (ref "U104") (pin "14") (pinfunction "BAT_14") (pintype "passive"))
      (node (ref "U105") (pin "A2") (pinfunction "VCC_A2") (pintype "passive"))
      (node (ref "U105") (pin "C2") (pinfunction "/RST_C2") (pintype "passive"))
    )
    (net (code "38") (name "VBUS") (class "Default")
      (node (ref "C101") (pin "1") (pinfunction "1_1") (pintype "passive"))
      (node (ref "C102") (pin "1") (pinfunction "1_1") (pintype "passive"))
      (node (ref "C103") (pin "1") (pinfunction "1_1") (pintype "passive"))
      (node (ref "C104") (pin "1") (pinfunction "1_1") (pintype "passive"))
      (node (ref "C117") (pin "1") (pinfunction "1_1") (pintype "passive"))
      (node (ref "C118") (pin "1") (pinfunction "1_1") (pintype "passive"))
      (node (ref "C119") (pin "1") (pinfunction "1_1") (pintype "passive"))
      (node (ref "FB100") (pin "2") (pinfunction "2_2") (pintype "passive"))
      (node (ref "FB101") (pin "2") (pinfunction "2_2") (pintype "passive"))
      (node (ref "R108") (pin "1") (pinfunction "1_1") (pintype "passive"))
      (node (ref "U104") (pin "1") (pinfunction "VBUS_1") (pintype "passive"))
      (node (ref "U104") (pin "24") (pinfunction "VBUS_24") (pintype "passive"))
    )
    (net (code "39") (name "V_SYS") (class "Default")
      (node (ref "C110") (pin "1") (pinfunction "1_1") (pintype "passive"))
      (node (ref "Q100") (pin "3") (pinfunction "D_3") (pintype "passive"))
      (node (ref "R107") (pin "1") (pinfunction "1_1") (pintype "passive"))
      (node (ref "R110") (pin "1") (pinfunction "1_1") (pintype "passive"))
      (node (ref "R113") (pin "1") (pinfunction "1_1") (pintype "passive"))
    )
    (net (code "40") (name "unconnected-(H100-Pad2)") (class "Default")
      (node (ref "H100") (pin "2") (pinfunction "2_2") (pintype "passive+no_connect"))
    )
    (net (code "41") (name "unconnected-(H100-SHIELD-PadS1)") (class "Default")
      (node (ref "H100") (pin "S1") (pinfunction "SHIELD_S1") (pintype "passive+no_connect"))
    )
    (net (code "42") (name "unconnected-(H100-SHIELD-PadS2)") (class "Default")
      (node (ref "H100") (pin "S2") (pinfunction "SHIELD_S2") (pintype "passive+no_connect"))
    )
    (net (code "43") (name "unconnected-(U100-RX1+-PadB11)") (class "Default")
      (node (ref "U100") (pin "B11") (pinfunction "RX1+_B11") (pintype "open_collector+no_connect"))
    )
    (net (code "44") (name "unconnected-(U100-RX1--PadB10)") (class "Default")
      (node (ref "U100") (pin "B10") (pinfunction "RX1-_B10") (pintype "open_collector+no_connect"))
    )
    (net (code "45") (name "unconnected-(U100-RX2+-PadA11)") (class "Default")
      (node (ref "U100") (pin "A11") (pinfunction "RX2+_A11") (pintype "open_collector+no_connect"))
    )
    (net (code "46") (name "unconnected-(U100-RX2--PadA10)") (class "Default")
      (node (ref "U100") (pin "A10") (pinfunction "RX2-_A10") (pintype "open_collector+no_connect"))
    )
    (net (code "47") (name "unconnected-(U100-SBU1-PadA8)") (class "Default")
      (node (ref "U100") (pin "A8") (pinfunction "SBU1_A8") (pintype "open_collector+no_connect"))
    )
    (net (code "48") (name "unconnected-(U100-SBU2-PadB8)") (class "Default")
      (node (ref "U100") (pin "B8") (pinfunction "SBU2_B8") (pintype "open_collector+no_connect"))
    )
    (net (code "49") (name "unconnected-(U100-SHIELD-PadSH1)") (class "Default")
      (node (ref "U100") (pin "SH1") (pinfunction "SHIELD_SH1") (pintype "passive+no_connect"))
    )
    (net (code "50") (name "unconnected-(U100-SHIELD-PadSH2)") (class "Default")
      (node (ref "U100") (pin "SH2") (pinfunction "SHIELD_SH2") (pintype "passive+no_connect"))
    )
    (net (code "51") (name "unconnected-(U100-SHIELD-PadSH3)") (class "Default")
      (node (ref "U100") (pin "SH3") (pinfunction "SHIELD_SH3") (pintype "passive+no_connect"))
    )
    (net (code "52") (name "unconnected-(U100-SHIELD-PadSH4)") (class "Default")
      (node (ref "U100") (pin "SH4") (pinfunction "SHIELD_SH4") (pintype "passive+no_connect"))
    )
    (net (code "53") (name "unconnected-(U100-TX1+-PadA2)") (class "Default")
      (node (ref "U100") (pin "A2") (pinfunction "TX1+_A2") (pintype "open_collector+no_connect"))
    )
    (net (code "54") (name "unconnected-(U100-TX1--PadA3)") (class "Default")
      (node (ref "U100") (pin "A3") (pinfunction "TX1-_A3") (pintype "open_collector+no_connect"))
    )
    (net (code "55") (name "unconnected-(U100-TX2+-PadB2)") (class "Default")
      (node (ref "U100") (pin "B2") (pinfunction "TX2+_B2") (pintype "open_collector+no_connect"))
    )
    (net (code "56") (name "unconnected-(U100-TX2--PadB3)") (class "Default")
      (node (ref "U100") (pin "B3") (pinfunction "TX2-_B3") (pintype "open_collector+no_connect"))
    )
    (net (code "57") (name "unconnected-(U102-Pad1)") (class "Default")
      (node (ref "U102") (pin "1") (pinfunction "1_1") (pintype "passive+no_connect"))
    )
    (net (code "58") (name "unconnected-(U102-Pad3)") (class "Default")
      (node (ref "U102") (pin "3") (pinfunction "3_3") (pintype "passive+no_connect"))
    )
    (net (code "59") (name "unconnected-(U104-QON-Pad12)") (class "Default")
      (node (ref "U104") (pin "12") (pinfunction "QON_12") (pintype "passive+no_connect"))
    )
    (net (code "60") (name "unconnected-(U105-CON-PadC1)") (class "Default")
      (node (ref "U105") (pin "C1") (pinfunction "CON_C1") (pintype "passive+no_connect"))
    )
    (net (code "61") (name "unconnected-(U105-DISC-PadA1)") (class "Default")
      (node (ref "U105") (pin "A1") (pinfunction "DISC_A1") (pintype "passive+no_connect"))
    )
  )
)
